# TabStopsDriver.net
KiCad netlist of a schematic drawn in EAGLE
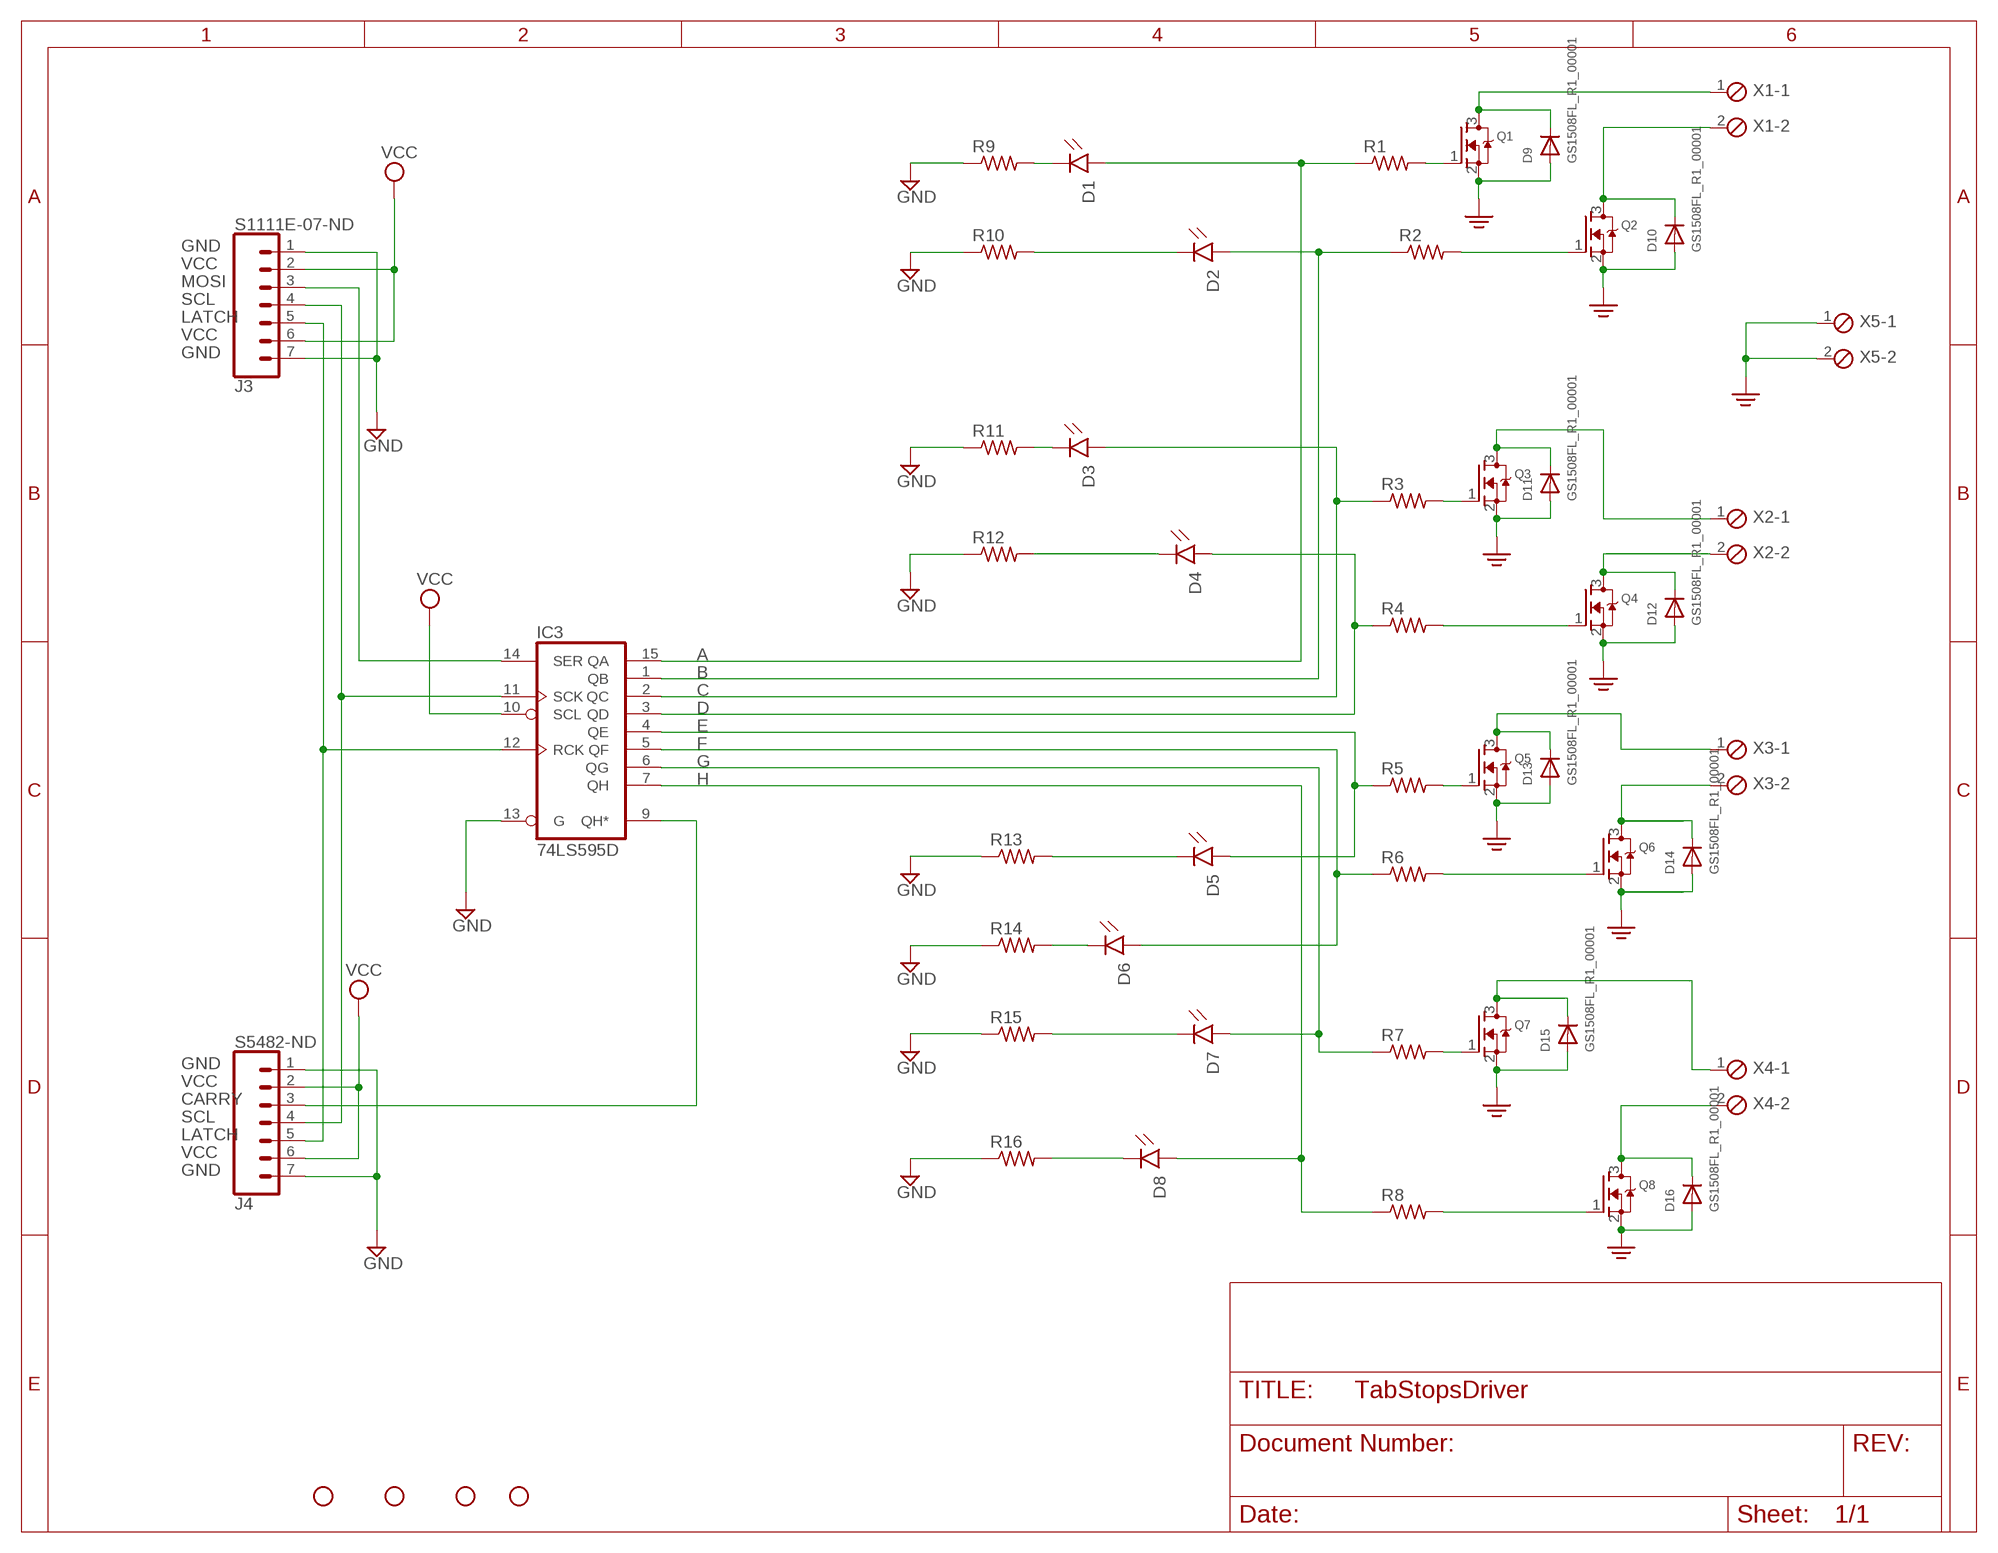
[diagram p0: schematic, sheet 1]

(export (version "E")
  (design (tool "Eeschema 10.0.6"))
  (components
    (comp (ref "D1")
      (value "B1911NB--20C005314U1930")
      (footprint "eagle-import:LEDC1608X95N_RND-R")
      (libsource (lib "eagle-import") (part "CHIP-ROUND-R_0603-1MM"))
    )
    (comp (ref "D2")
      (value "B1911NB--20C005314U1930")
      (footprint "eagle-import:LEDC1608X95N_RND-R")
      (libsource (lib "eagle-import") (part "CHIP-ROUND-R_0603-1MM"))
    )
    (comp (ref "D3")
      (value "B1911NB--20C005314U1930")
      (footprint "eagle-import:LEDC1608X95N_RND-R")
      (libsource (lib "eagle-import") (part "CHIP-ROUND-R_0603-1MM"))
    )
    (comp (ref "D4")
      (value "B1911NB--20C005314U1930")
      (footprint "eagle-import:LEDC1608X95N_RND-R")
      (libsource (lib "eagle-import") (part "CHIP-ROUND-R_0603-1MM"))
    )
    (comp (ref "D5")
      (value "B1911NB--20C005314U1930")
      (footprint "eagle-import:LEDC1608X95N_RND-R")
      (libsource (lib "eagle-import") (part "CHIP-ROUND-R_0603-1MM"))
    )
    (comp (ref "D6")
      (value "B1911NB--20C005314U1930")
      (footprint "eagle-import:LEDC1608X95N_RND-R")
      (libsource (lib "eagle-import") (part "CHIP-ROUND-R_0603-1MM"))
    )
    (comp (ref "D7")
      (value "B1911NB--20C005314U1930")
      (footprint "eagle-import:LEDC1608X95N_RND-R")
      (libsource (lib "eagle-import") (part "CHIP-ROUND-R_0603-1MM"))
    )
    (comp (ref "D8")
      (value "B1911NB--20C005314U1930")
      (footprint "eagle-import:LEDC1608X95N_RND-R")
      (libsource (lib "eagle-import") (part "CHIP-ROUND-R_0603-1MM"))
    )
    (comp (ref "D9")
      (value "GS1508FL_R1_00001")
      (footprint "eagle-import:SOD-123FL")
      (libsource (lib "eagle-import") (part "DIODE_SOD-123FL"))
    )
    (comp (ref "D10")
      (value "GS1508FL_R1_00001")
      (footprint "eagle-import:SOD-123FL")
      (libsource (lib "eagle-import") (part "DIODE_SOD-123FL"))
    )
    (comp (ref "D11")
      (value "GS1508FL_R1_00001")
      (footprint "eagle-import:SOD-123FL")
      (libsource (lib "eagle-import") (part "DIODE_SOD-123FL"))
    )
    (comp (ref "D12")
      (value "GS1508FL_R1_00001")
      (footprint "eagle-import:SOD-123FL")
      (libsource (lib "eagle-import") (part "DIODE_SOD-123FL"))
    )
    (comp (ref "D13")
      (value "GS1508FL_R1_00001")
      (footprint "eagle-import:SOD-123FL")
      (libsource (lib "eagle-import") (part "DIODE_SOD-123FL"))
    )
    (comp (ref "D14")
      (value "GS1508FL_R1_00001")
      (footprint "eagle-import:SOD-123FL")
      (libsource (lib "eagle-import") (part "DIODE_SOD-123FL"))
    )
    (comp (ref "D15")
      (value "GS1508FL_R1_00001")
      (footprint "eagle-import:SOD-123FL")
      (libsource (lib "eagle-import") (part "DIODE_SOD-123FL"))
    )
    (comp (ref "D16")
      (value "GS1508FL_R1_00001")
      (footprint "eagle-import:SOD-123FL")
      (libsource (lib "eagle-import") (part "DIODE_SOD-123FL"))
    )
    (comp (ref "H1")
      (value "STAND-OFF")
      (footprint "eagle-import:STAND-OFF")
      (libsource (lib "eagle-import") (part "STAND-OFF"))
    )
    (comp (ref "H2")
      (value "STAND-OFF")
      (footprint "eagle-import:STAND-OFF")
      (libsource (lib "eagle-import") (part "STAND-OFF"))
    )
    (comp (ref "H3")
      (value "STAND-OFF")
      (footprint "eagle-import:STAND-OFF")
      (libsource (lib "eagle-import") (part "STAND-OFF"))
    )
    (comp (ref "H4")
      (value "STAND-OFF")
      (footprint "eagle-import:STAND-OFF")
      (libsource (lib "eagle-import") (part "STAND-OFF"))
    )
    (comp (ref "IC3")
      (value "74LS595D")
      (footprint "eagle-import:SO16")
      (libsource (lib "eagle-import") (part "74595DLS"))
    )
    (comp (ref "J3")
      (value "S1111E-07-ND")
      (footprint "eagle-import:1X07_LONGPADS")
      (libsource (lib "eagle-import") (part "CONN_07LONGPADS"))
    )
    (comp (ref "J4")
      (value "S5482-ND")
      (footprint "eagle-import:1X07_LONGPADS")
      (libsource (lib "eagle-import") (part "CONN_07LONGPADS"))
    )
    (comp (ref "Q1")
      (value "3757-PJA3416A_R1_00001CT-ND")
      (footprint "eagle-import:SOT23")
      (libsource (lib "eagle-import") (part "MOSFET-NREFLOW"))
    )
    (comp (ref "Q2")
      (value "3757-PJA3416A_R1_00001CT-ND")
      (footprint "eagle-import:SOT23")
      (libsource (lib "eagle-import") (part "MOSFET-NREFLOW"))
    )
    (comp (ref "Q3")
      (value "3757-PJA3416A_R1_00001CT-ND")
      (footprint "eagle-import:SOT23")
      (libsource (lib "eagle-import") (part "MOSFET-NREFLOW"))
    )
    (comp (ref "Q4")
      (value "3757-PJA3416A_R1_00001CT-ND")
      (footprint "eagle-import:SOT23")
      (libsource (lib "eagle-import") (part "MOSFET-NREFLOW"))
    )
    (comp (ref "Q5")
      (value "3757-PJA3416A_R1_00001CT-ND")
      (footprint "eagle-import:SOT23")
      (libsource (lib "eagle-import") (part "MOSFET-NREFLOW"))
    )
    (comp (ref "Q6")
      (value "3757-PJA3416A_R1_00001CT-ND")
      (footprint "eagle-import:SOT23")
      (libsource (lib "eagle-import") (part "MOSFET-NREFLOW"))
    )
    (comp (ref "Q7")
      (value "3757-PJA3416A_R1_00001CT-ND")
      (footprint "eagle-import:SOT23")
      (libsource (lib "eagle-import") (part "MOSFET-NREFLOW"))
    )
    (comp (ref "Q8")
      (value "3757-PJA3416A_R1_00001CT-ND")
      (footprint "eagle-import:SOT23")
      (libsource (lib "eagle-import") (part "MOSFET-NREFLOW"))
    )
    (comp (ref "R1")
      (value "RMCF0805FT100RCT-ND")
      (footprint "eagle-import:R0805")
      (libsource (lib "eagle-import") (part "R-US_R0805"))
    )
    (comp (ref "R2")
      (value "RMCF0805FT100RCT-ND")
      (footprint "eagle-import:R0805")
      (libsource (lib "eagle-import") (part "R-US_R0805"))
    )
    (comp (ref "R3")
      (value "RMCF0805FT100RCT-ND")
      (footprint "eagle-import:R0805")
      (libsource (lib "eagle-import") (part "R-US_R0805"))
    )
    (comp (ref "R4")
      (value "RMCF0805FT100RCT-ND")
      (footprint "eagle-import:R0805")
      (libsource (lib "eagle-import") (part "R-US_R0805"))
    )
    (comp (ref "R5")
      (value "RMCF0805FT100RCT-ND")
      (footprint "eagle-import:R0805")
      (libsource (lib "eagle-import") (part "R-US_R0805"))
    )
    (comp (ref "R6")
      (value "RMCF0805FT100RCT-ND")
      (footprint "eagle-import:R0805")
      (libsource (lib "eagle-import") (part "R-US_R0805"))
    )
    (comp (ref "R7")
      (value "RMCF0805FT100RCT-ND")
      (footprint "eagle-import:R0805")
      (libsource (lib "eagle-import") (part "R-US_R0805"))
    )
    (comp (ref "R8")
      (value "RMCF0805FT100RCT-ND")
      (footprint "eagle-import:R0805")
      (libsource (lib "eagle-import") (part "R-US_R0805"))
    )
    (comp (ref "R9")
      (value "RMCF0805FT1K50CT-ND")
      (footprint "eagle-import:R0805")
      (libsource (lib "eagle-import") (part "R-US_R0805"))
    )
    (comp (ref "R10")
      (value "RMCF0805FT1K50CT-ND")
      (footprint "eagle-import:R0805")
      (libsource (lib "eagle-import") (part "R-US_R0805"))
    )
    (comp (ref "R11")
      (value "RMCF0805FT1K50CT-ND")
      (footprint "eagle-import:R0805")
      (libsource (lib "eagle-import") (part "R-US_R0805"))
    )
    (comp (ref "R12")
      (value "RMCF0805FT1K50CT-ND")
      (footprint "eagle-import:R0805")
      (libsource (lib "eagle-import") (part "R-US_R0805"))
    )
    (comp (ref "R13")
      (value "RMCF0805FT1K50CT-ND")
      (footprint "eagle-import:R0805")
      (libsource (lib "eagle-import") (part "R-US_R0805"))
    )
    (comp (ref "R14")
      (value "RMCF0805FT1K50CT-ND")
      (footprint "eagle-import:R0805")
      (libsource (lib "eagle-import") (part "R-US_R0805"))
    )
    (comp (ref "R15")
      (value "RMCF0805FT1K50CT-ND")
      (footprint "eagle-import:R0805")
      (libsource (lib "eagle-import") (part "R-US_R0805"))
    )
    (comp (ref "R16")
      (value "RMCF0805FT1K50CT-ND")
      (footprint "eagle-import:R0805")
      (libsource (lib "eagle-import") (part "R-US_R0805"))
    )
    (comp (ref "X1")
      (value "277-6156-ND")
      (footprint "eagle-import:2POL254")
      (libsource (lib "eagle-import") (part "MPT2"))
    )
    (comp (ref "X2")
      (value "277-6156-ND")
      (footprint "eagle-import:2POL254")
      (libsource (lib "eagle-import") (part "MPT2"))
    )
    (comp (ref "X3")
      (value "277-6156-ND")
      (footprint "eagle-import:2POL254")
      (libsource (lib "eagle-import") (part "MPT2"))
    )
    (comp (ref "X4")
      (value "277-6156-ND")
      (footprint "eagle-import:2POL254")
      (libsource (lib "eagle-import") (part "MPT2"))
    )
    (comp (ref "X5")
      (value "277-6156-ND")
      (footprint "eagle-import:2POL254")
      (libsource (lib "eagle-import") (part "MPT2"))
    )
  )
  (nets
    (net (code "1") (name "/A") (class "Default")
      (node (ref "D1") (pin "A") (pinfunction "A_A") (pintype "passive"))
      (node (ref "IC3") (pin "15") (pinfunction "QA_15") (pintype "tri_state"))
      (node (ref "R1") (pin "1") (pinfunction "1_1") (pintype "passive"))
    )
    (net (code "2") (name "/B") (class "Default")
      (node (ref "D2") (pin "A") (pinfunction "A_A") (pintype "passive"))
      (node (ref "IC3") (pin "1") (pinfunction "QB_1") (pintype "tri_state"))
      (node (ref "R2") (pin "1") (pinfunction "1_1") (pintype "passive"))
    )
    (net (code "3") (name "/C") (class "Default")
      (node (ref "D3") (pin "A") (pinfunction "A_A") (pintype "passive"))
      (node (ref "IC3") (pin "2") (pinfunction "QC_2") (pintype "tri_state"))
      (node (ref "R3") (pin "1") (pinfunction "1_1") (pintype "passive"))
    )
    (net (code "4") (name "/CARRY") (class "Default")
      (node (ref "IC3") (pin "9") (pinfunction "QH*_9") (pintype "tri_state"))
      (node (ref "J4") (pin "3") (pinfunction "3_3") (pintype "passive"))
    )
    (net (code "5") (name "/D") (class "Default")
      (node (ref "D4") (pin "A") (pinfunction "A_A") (pintype "passive"))
      (node (ref "IC3") (pin "3") (pinfunction "QD_3") (pintype "tri_state"))
      (node (ref "R4") (pin "1") (pinfunction "1_1") (pintype "passive"))
    )
    (net (code "6") (name "/E") (class "Default")
      (node (ref "D5") (pin "A") (pinfunction "A_A") (pintype "passive"))
      (node (ref "IC3") (pin "4") (pinfunction "QE_4") (pintype "tri_state"))
      (node (ref "R5") (pin "1") (pinfunction "1_1") (pintype "passive"))
    )
    (net (code "7") (name "/F") (class "Default")
      (node (ref "D6") (pin "A") (pinfunction "A_A") (pintype "passive"))
      (node (ref "IC3") (pin "5") (pinfunction "QF_5") (pintype "tri_state"))
      (node (ref "R6") (pin "1") (pinfunction "1_1") (pintype "passive"))
    )
    (net (code "8") (name "/G") (class "Default")
      (node (ref "D7") (pin "A") (pinfunction "A_A") (pintype "passive"))
      (node (ref "IC3") (pin "6") (pinfunction "QG_6") (pintype "tri_state"))
      (node (ref "R7") (pin "1") (pinfunction "1_1") (pintype "passive"))
    )
    (net (code "9") (name "/H") (class "Default")
      (node (ref "D8") (pin "A") (pinfunction "A_A") (pintype "passive"))
      (node (ref "IC3") (pin "7") (pinfunction "QH_7") (pintype "tri_state"))
      (node (ref "R8") (pin "1") (pinfunction "1_1") (pintype "passive"))
    )
    (net (code "10") (name "/LATCH") (class "Default")
      (node (ref "IC3") (pin "12") (pinfunction "RCK_12") (pintype "input"))
      (node (ref "J3") (pin "5") (pinfunction "5_5") (pintype "passive"))
      (node (ref "J4") (pin "5") (pinfunction "5_5") (pintype "passive"))
    )
    (net (code "11") (name "/MOSI") (class "Default")
      (node (ref "IC3") (pin "14") (pinfunction "SER_14") (pintype "input"))
      (node (ref "J3") (pin "3") (pinfunction "3_3") (pintype "passive"))
    )
    (net (code "12") (name "/SCL") (class "Default")
      (node (ref "IC3") (pin "11") (pinfunction "SCK_11") (pintype "input"))
      (node (ref "J3") (pin "4") (pinfunction "4_4") (pintype "passive"))
      (node (ref "J4") (pin "4") (pinfunction "4_4") (pintype "passive"))
    )
    (net (code "13") (name "EGND") (class "Default")
      (node (ref "D10") (pin "A") (pinfunction "A_A") (pintype "passive"))
      (node (ref "D11") (pin "A") (pinfunction "A_A") (pintype "passive"))
      (node (ref "D12") (pin "A") (pinfunction "A_A") (pintype "passive"))
      (node (ref "D13") (pin "A") (pinfunction "A_A") (pintype "passive"))
      (node (ref "D14") (pin "A") (pinfunction "A_A") (pintype "passive"))
      (node (ref "D15") (pin "A") (pinfunction "A_A") (pintype "passive"))
      (node (ref "D16") (pin "A") (pinfunction "A_A") (pintype "passive"))
      (node (ref "D9") (pin "A") (pinfunction "A_A") (pintype "passive"))
      (node (ref "Q1") (pin "2") (pinfunction "S_2") (pintype "bidirectional"))
      (node (ref "Q2") (pin "2") (pinfunction "S_2") (pintype "bidirectional"))
      (node (ref "Q3") (pin "2") (pinfunction "S_2") (pintype "bidirectional"))
      (node (ref "Q4") (pin "2") (pinfunction "S_2") (pintype "bidirectional"))
      (node (ref "Q5") (pin "2") (pinfunction "S_2") (pintype "bidirectional"))
      (node (ref "Q6") (pin "2") (pinfunction "S_2") (pintype "bidirectional"))
      (node (ref "Q7") (pin "2") (pinfunction "S_2") (pintype "bidirectional"))
      (node (ref "Q8") (pin "2") (pinfunction "S_2") (pintype "bidirectional"))
      (node (ref "X5") (pin "1") (pinfunction "1_1") (pintype "passive"))
      (node (ref "X5") (pin "2") (pinfunction "1_2") (pintype "passive"))
    )
    (net (code "14") (name "GND") (class "Default")
      (node (ref "IC3") (pin "13") (pinfunction "G_13") (pintype "input"))
      (node (ref "J3") (pin "1") (pinfunction "1_1") (pintype "passive"))
      (node (ref "J3") (pin "7") (pinfunction "7_7") (pintype "passive"))
      (node (ref "J4") (pin "1") (pinfunction "1_1") (pintype "passive"))
      (node (ref "J4") (pin "7") (pinfunction "7_7") (pintype "passive"))
      (node (ref "R10") (pin "1") (pinfunction "1_1") (pintype "passive"))
      (node (ref "R11") (pin "1") (pinfunction "1_1") (pintype "passive"))
      (node (ref "R12") (pin "1") (pinfunction "1_1") (pintype "passive"))
      (node (ref "R13") (pin "1") (pinfunction "1_1") (pintype "passive"))
      (node (ref "R14") (pin "1") (pinfunction "1_1") (pintype "passive"))
      (node (ref "R15") (pin "1") (pinfunction "1_1") (pintype "passive"))
      (node (ref "R16") (pin "1") (pinfunction "1_1") (pintype "passive"))
      (node (ref "R9") (pin "1") (pinfunction "1_1") (pintype "passive"))
    )
    (net (code "15") (name "Net-(D1-PadC)") (class "Default")
      (node (ref "D1") (pin "C") (pinfunction "C_C") (pintype "passive"))
      (node (ref "R9") (pin "2") (pinfunction "2_2") (pintype "passive"))
    )
    (net (code "16") (name "Net-(D2-PadC)") (class "Default")
      (node (ref "D2") (pin "C") (pinfunction "C_C") (pintype "passive"))
      (node (ref "R10") (pin "2") (pinfunction "2_2") (pintype "passive"))
    )
    (net (code "17") (name "Net-(D3-PadC)") (class "Default")
      (node (ref "D3") (pin "C") (pinfunction "C_C") (pintype "passive"))
      (node (ref "R11") (pin "2") (pinfunction "2_2") (pintype "passive"))
    )
    (net (code "18") (name "Net-(D4-PadC)") (class "Default")
      (node (ref "D4") (pin "C") (pinfunction "C_C") (pintype "passive"))
      (node (ref "R12") (pin "2") (pinfunction "2_2") (pintype "passive"))
    )
    (net (code "19") (name "Net-(D5-PadC)") (class "Default")
      (node (ref "D5") (pin "C") (pinfunction "C_C") (pintype "passive"))
      (node (ref "R13") (pin "2") (pinfunction "2_2") (pintype "passive"))
    )
    (net (code "20") (name "Net-(D6-PadC)") (class "Default")
      (node (ref "D6") (pin "C") (pinfunction "C_C") (pintype "passive"))
      (node (ref "R14") (pin "2") (pinfunction "2_2") (pintype "passive"))
    )
    (net (code "21") (name "Net-(D7-PadC)") (class "Default")
      (node (ref "D7") (pin "C") (pinfunction "C_C") (pintype "passive"))
      (node (ref "R15") (pin "2") (pinfunction "2_2") (pintype "passive"))
    )
    (net (code "22") (name "Net-(D8-PadC)") (class "Default")
      (node (ref "D8") (pin "C") (pinfunction "C_C") (pintype "passive"))
      (node (ref "R16") (pin "2") (pinfunction "2_2") (pintype "passive"))
    )
    (net (code "23") (name "Net-(Q1-D)") (class "Default")
      (node (ref "D9") (pin "C") (pinfunction "C_C") (pintype "passive"))
      (node (ref "Q1") (pin "3") (pinfunction "D_3") (pintype "bidirectional"))
      (node (ref "X1") (pin "1") (pinfunction "1_1") (pintype "passive"))
    )
    (net (code "24") (name "Net-(Q1-G)") (class "Default")
      (node (ref "Q1") (pin "1") (pinfunction "G_1") (pintype "bidirectional"))
      (node (ref "R1") (pin "2") (pinfunction "2_2") (pintype "passive"))
    )
    (net (code "25") (name "Net-(Q2-D)") (class "Default")
      (node (ref "D10") (pin "C") (pinfunction "C_C") (pintype "passive"))
      (node (ref "Q2") (pin "3") (pinfunction "D_3") (pintype "bidirectional"))
      (node (ref "X1") (pin "2") (pinfunction "1_2") (pintype "passive"))
    )
    (net (code "26") (name "Net-(Q2-G)") (class "Default")
      (node (ref "Q2") (pin "1") (pinfunction "G_1") (pintype "bidirectional"))
      (node (ref "R2") (pin "2") (pinfunction "2_2") (pintype "passive"))
    )
    (net (code "27") (name "Net-(Q3-D)") (class "Default")
      (node (ref "D11") (pin "C") (pinfunction "C_C") (pintype "passive"))
      (node (ref "Q3") (pin "3") (pinfunction "D_3") (pintype "bidirectional"))
      (node (ref "X2") (pin "1") (pinfunction "1_1") (pintype "passive"))
    )
    (net (code "28") (name "Net-(Q3-G)") (class "Default")
      (node (ref "Q3") (pin "1") (pinfunction "G_1") (pintype "bidirectional"))
      (node (ref "R3") (pin "2") (pinfunction "2_2") (pintype "passive"))
    )
    (net (code "29") (name "Net-(Q4-D)") (class "Default")
      (node (ref "D12") (pin "C") (pinfunction "C_C") (pintype "passive"))
      (node (ref "Q4") (pin "3") (pinfunction "D_3") (pintype "bidirectional"))
      (node (ref "X2") (pin "2") (pinfunction "1_2") (pintype "passive"))
    )
    (net (code "30") (name "Net-(Q4-G)") (class "Default")
      (node (ref "Q4") (pin "1") (pinfunction "G_1") (pintype "bidirectional"))
      (node (ref "R4") (pin "2") (pinfunction "2_2") (pintype "passive"))
    )
    (net (code "31") (name "Net-(Q5-D)") (class "Default")
      (node (ref "D13") (pin "C") (pinfunction "C_C") (pintype "passive"))
      (node (ref "Q5") (pin "3") (pinfunction "D_3") (pintype "bidirectional"))
      (node (ref "X3") (pin "1") (pinfunction "1_1") (pintype "passive"))
    )
    (net (code "32") (name "Net-(Q5-G)") (class "Default")
      (node (ref "Q5") (pin "1") (pinfunction "G_1") (pintype "bidirectional"))
      (node (ref "R5") (pin "2") (pinfunction "2_2") (pintype "passive"))
    )
    (net (code "33") (name "Net-(Q6-D)") (class "Default")
      (node (ref "D14") (pin "C") (pinfunction "C_C") (pintype "passive"))
      (node (ref "Q6") (pin "3") (pinfunction "D_3") (pintype "bidirectional"))
      (node (ref "X3") (pin "2") (pinfunction "1_2") (pintype "passive"))
    )
    (net (code "34") (name "Net-(Q6-G)") (class "Default")
      (node (ref "Q6") (pin "1") (pinfunction "G_1") (pintype "bidirectional"))
      (node (ref "R6") (pin "2") (pinfunction "2_2") (pintype "passive"))
    )
    (net (code "35") (name "Net-(Q7-D)") (class "Default")
      (node (ref "D15") (pin "C") (pinfunction "C_C") (pintype "passive"))
      (node (ref "Q7") (pin "3") (pinfunction "D_3") (pintype "bidirectional"))
      (node (ref "X4") (pin "1") (pinfunction "1_1") (pintype "passive"))
    )
    (net (code "36") (name "Net-(Q7-G)") (class "Default")
      (node (ref "Q7") (pin "1") (pinfunction "G_1") (pintype "bidirectional"))
      (node (ref "R7") (pin "2") (pinfunction "2_2") (pintype "passive"))
    )
    (net (code "37") (name "Net-(Q8-D)") (class "Default")
      (node (ref "D16") (pin "C") (pinfunction "C_C") (pintype "passive"))
      (node (ref "Q8") (pin "3") (pinfunction "D_3") (pintype "bidirectional"))
      (node (ref "X4") (pin "2") (pinfunction "1_2") (pintype "passive"))
    )
    (net (code "38") (name "Net-(Q8-G)") (class "Default")
      (node (ref "Q8") (pin "1") (pinfunction "G_1") (pintype "bidirectional"))
      (node (ref "R8") (pin "2") (pinfunction "2_2") (pintype "passive"))
    )
    (net (code "39") (name "VCC") (class "Default")
      (node (ref "IC3") (pin "10") (pinfunction "SCL_10") (pintype "input"))
      (node (ref "J3") (pin "2") (pinfunction "2_2") (pintype "passive"))
      (node (ref "J3") (pin "6") (pinfunction "6_6") (pintype "passive"))
      (node (ref "J4") (pin "2") (pinfunction "2_2") (pintype "passive"))
      (node (ref "J4") (pin "6") (pinfunction "6_6") (pintype "passive"))
    )
  )
)
